# LilyPad_Light_Sensor.net
KiCad netlist of a schematic drawn in EAGLE
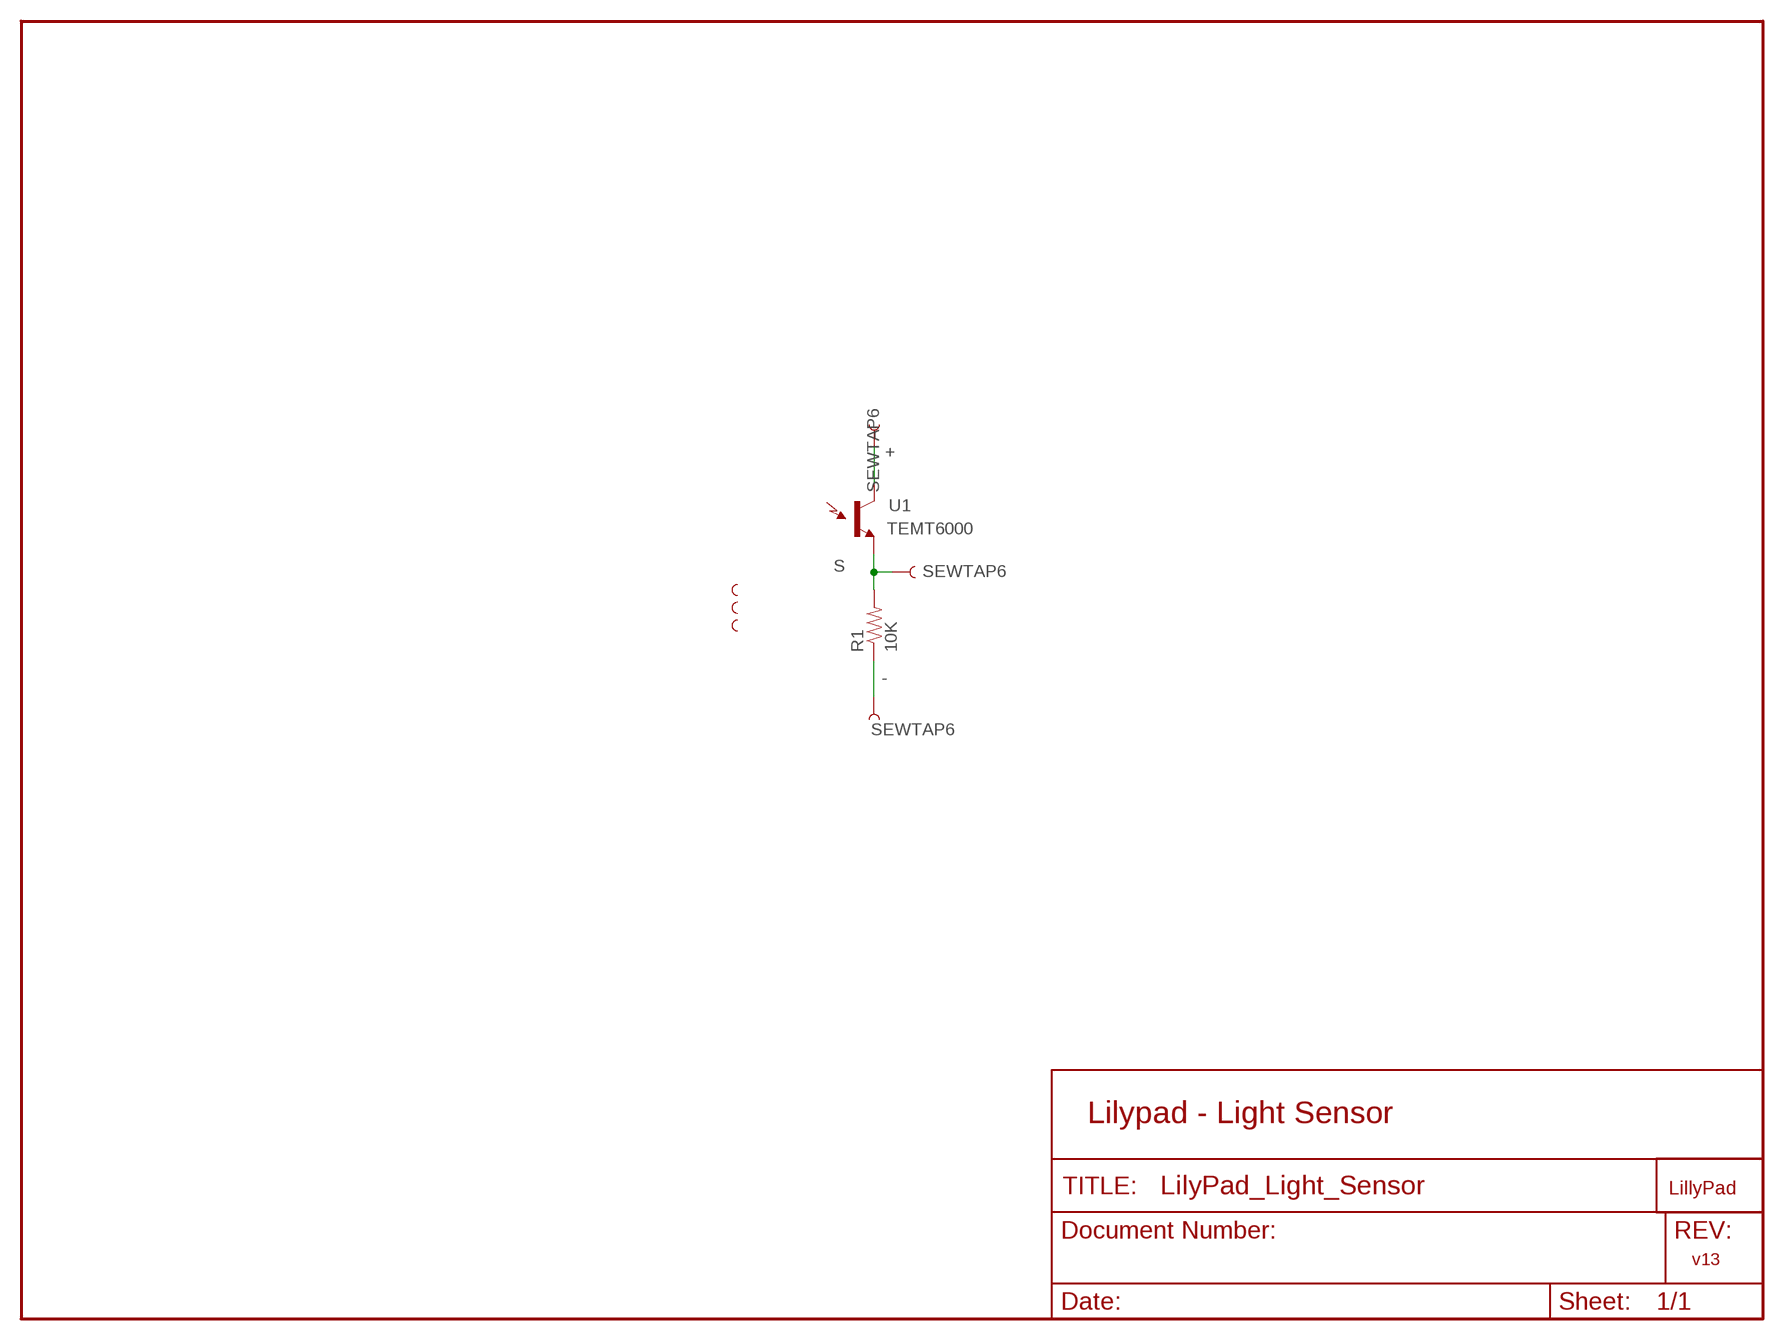
[diagram p0: schematic, sheet 1]

(export (version "E")
  (design (tool "Eeschema 10.0.6"))
  (components
    (comp (ref "LIGHT+")
      (value "SEWTAP6")
      (footprint "eagle-import:PETAL-SMALL-2SIDE")
      (libsource (lib "eagle-import") (part "SEWTAP6"))
    )
    (comp (ref "LIGHT-")
      (value "SEWTAP6")
      (footprint "eagle-import:PETAL-SMALL-2SIDE")
      (libsource (lib "eagle-import") (part "SEWTAP6"))
    )
    (comp (ref "LIGHT1")
      (value "SEWTAP-NOHOLE2")
      (footprint "eagle-import:PETAL-NOHOLE-2SIDE")
      (libsource (lib "eagle-import") (part "SEWTAP-NOHOLE2"))
    )
    (comp (ref "LIGHT2")
      (value "SEWTAP-NOHOLE2")
      (footprint "eagle-import:PETAL-NOHOLE-2SIDE")
      (libsource (lib "eagle-import") (part "SEWTAP-NOHOLE2"))
    )
    (comp (ref "LIGHT3")
      (value "SEWTAP-NOHOLE2")
      (footprint "eagle-import:PETAL-NOHOLE-2SIDE")
      (libsource (lib "eagle-import") (part "SEWTAP-NOHOLE2"))
    )
    (comp (ref "LIGHTS")
      (value "SEWTAP6")
      (footprint "eagle-import:PETAL-SMALL-2SIDE")
      (libsource (lib "eagle-import") (part "SEWTAP6"))
    )
    (comp (ref "R1")
      (value "10K")
      (footprint "eagle-import:C0402")
      (libsource (lib "eagle-import") (part "RESISTOR0402"))
    )
    (comp (ref "U$2")
      (value "LOGO-LPLP")
      (footprint "eagle-import:LOGO-LILYPAD")
      (libsource (lib "eagle-import") (part "LOGO-LPLP"))
    )
    (comp (ref "U1")
      (value "TEMT6000")
      (footprint "eagle-import:TEMT6000-SEN")
      (libsource (lib "eagle-import") (part "TEMT6000"))
    )
  )
  (nets
    (net (code "1") (name "/+") (class "Default")
      (node (ref "LIGHT+") (pin "1") (pinfunction "1_1") (pintype "bidirectional"))
      (node (ref "U1") (pin "COLLECTOR") (pinfunction "C1_COLLECTOR") (pintype "passive"))
    )
    (net (code "2") (name "/-") (class "Default")
      (node (ref "LIGHT-") (pin "1") (pinfunction "1_1") (pintype "bidirectional"))
      (node (ref "R1") (pin "1") (pinfunction "1_1") (pintype "passive"))
    )
    (net (code "3") (name "/S") (class "Default")
      (node (ref "LIGHTS") (pin "1") (pinfunction "1_1") (pintype "bidirectional"))
      (node (ref "R1") (pin "2") (pinfunction "2_2") (pintype "passive"))
      (node (ref "U1") (pin "EMITTER") (pinfunction "E1_EMITTER") (pintype "passive"))
    )
  )
)
